# DRV_RGB.net
KiCad netlist of a schematic drawn in EAGLE
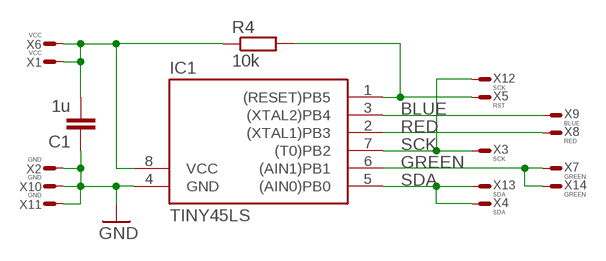
[diagram p0: schematic, sheet 1]

(export (version "E")
  (design (tool "Eeschema 10.0.6"))
  (components
    (comp (ref "C1")
      (value "1u")
      (footprint "eagle-import:0603")
      (libsource (lib "eagle-import") (part "C0603"))
    )
    (comp (ref "IC1")
      (value "TINY45LS")
      (footprint "eagle-import:SOIC8")
      (libsource (lib "eagle-import") (part "TINY11SL"))
    )
    (comp (ref "R4")
      (value "10k")
      (footprint "eagle-import:0603")
      (libsource (lib "eagle-import") (part "R0603"))
    )
    (comp (ref "X1")
      (value "VCC")
      (footprint "eagle-import:T1.6_0.9")
      (libsource (lib "eagle-import") (part "WIREPADT1.6/0.9"))
    )
    (comp (ref "X2")
      (value "GND")
      (footprint "eagle-import:T1.6_0.9")
      (libsource (lib "eagle-import") (part "WIREPADT1.6/0.9"))
    )
    (comp (ref "X3")
      (value "SCK")
      (footprint "eagle-import:T1.6_0.9")
      (libsource (lib "eagle-import") (part "WIREPADT1.6/0.9"))
    )
    (comp (ref "X4")
      (value "SDA")
      (footprint "eagle-import:T1.6_0.9")
      (libsource (lib "eagle-import") (part "WIREPADT1.6/0.9"))
    )
    (comp (ref "X5")
      (value "RST")
      (footprint "eagle-import:T1.6_0.9")
      (libsource (lib "eagle-import") (part "WIREPADT1.6/0.9"))
    )
    (comp (ref "X6")
      (value "VCC")
      (footprint "eagle-import:T1.6_0.9")
      (libsource (lib "eagle-import") (part "WIREPADT1.6/0.9"))
    )
    (comp (ref "X7")
      (value "GREEN")
      (footprint "eagle-import:T1.6_0.9")
      (libsource (lib "eagle-import") (part "WIREPADT1.6/0.9"))
    )
    (comp (ref "X8")
      (value "RED")
      (footprint "eagle-import:T1.6_0.9")
      (libsource (lib "eagle-import") (part "WIREPADT1.6/0.9"))
    )
    (comp (ref "X9")
      (value "BLUE")
      (footprint "eagle-import:T1.6_0.9")
      (libsource (lib "eagle-import") (part "WIREPADT1.6/0.9"))
    )
    (comp (ref "X10")
      (value "GND")
      (footprint "eagle-import:T1.6_0.9")
      (libsource (lib "eagle-import") (part "WIREPADT1.6/0.9"))
    )
    (comp (ref "X11")
      (value "GND")
      (footprint "eagle-import:T1.6_0.9")
      (libsource (lib "eagle-import") (part "WIREPADT1.6/0.9"))
    )
    (comp (ref "X12")
      (value "SCK")
      (footprint "eagle-import:T1.6_0.9")
      (libsource (lib "eagle-import") (part "WIREPADT1.6/0.9"))
    )
    (comp (ref "X13")
      (value "SDA")
      (footprint "eagle-import:T1.6_0.9")
      (libsource (lib "eagle-import") (part "WIREPADT1.6/0.9"))
    )
    (comp (ref "X14")
      (value "GREEN")
      (footprint "eagle-import:T1.6_0.9")
      (libsource (lib "eagle-import") (part "WIREPADT1.6/0.9"))
    )
  )
  (nets
    (net (code "1") (name "/BLUE") (class "Default")
      (node (ref "IC1") (pin "3") (pinfunction "(XTAL2)PB4_3") (pintype "bidirectional"))
      (node (ref "X9") (pin "1") (pinfunction "S_1") (pintype "passive"))
    )
    (net (code "2") (name "/GREEN") (class "Default")
      (node (ref "IC1") (pin "6") (pinfunction "(AIN1)PB1_6") (pintype "bidirectional"))
      (node (ref "X14") (pin "1") (pinfunction "S_1") (pintype "passive"))
      (node (ref "X7") (pin "1") (pinfunction "S_1") (pintype "passive"))
    )
    (net (code "3") (name "/RED") (class "Default")
      (node (ref "IC1") (pin "2") (pinfunction "(XTAL1)PB3_2") (pintype "bidirectional"))
      (node (ref "X8") (pin "1") (pinfunction "S_1") (pintype "passive"))
    )
    (net (code "4") (name "/SCK") (class "Default")
      (node (ref "IC1") (pin "7") (pinfunction "(T0)PB2_7") (pintype "bidirectional"))
      (node (ref "X12") (pin "1") (pinfunction "S_1") (pintype "passive"))
      (node (ref "X3") (pin "1") (pinfunction "S_1") (pintype "passive"))
    )
    (net (code "5") (name "/SDA") (class "Default")
      (node (ref "IC1") (pin "5") (pinfunction "(AIN0)PB0_5") (pintype "bidirectional"))
      (node (ref "X13") (pin "1") (pinfunction "S_1") (pintype "passive"))
      (node (ref "X4") (pin "1") (pinfunction "S_1") (pintype "passive"))
    )
    (net (code "6") (name "GND") (class "Default")
      (node (ref "C1") (pin "1") (pinfunction "1_1") (pintype "passive"))
      (node (ref "IC1") (pin "4") (pinfunction "GND_4") (pintype "power_in"))
      (node (ref "X10") (pin "1") (pinfunction "S_1") (pintype "passive"))
      (node (ref "X11") (pin "1") (pinfunction "S_1") (pintype "passive"))
      (node (ref "X2") (pin "1") (pinfunction "S_1") (pintype "passive"))
    )
    (net (code "7") (name "Net-(IC1-(RESET)PB5)") (class "Default")
      (node (ref "IC1") (pin "1") (pinfunction "(RESET)PB5_1") (pintype "bidirectional"))
      (node (ref "R4") (pin "2") (pinfunction "2_2") (pintype "passive"))
      (node (ref "X5") (pin "1") (pinfunction "S_1") (pintype "passive"))
    )
    (net (code "8") (name "Net-(IC1-VCC)") (class "Default")
      (node (ref "C1") (pin "2") (pinfunction "2_2") (pintype "passive"))
      (node (ref "IC1") (pin "8") (pinfunction "VCC_8") (pintype "power_in"))
      (node (ref "R4") (pin "1") (pinfunction "1_1") (pintype "passive"))
      (node (ref "X1") (pin "1") (pinfunction "S_1") (pintype "passive"))
      (node (ref "X6") (pin "1") (pinfunction "S_1") (pintype "passive"))
    )
  )
)
